# ATSAMD09D14_Breakout_rev_B.net
KiCad netlist of a schematic drawn in EAGLE
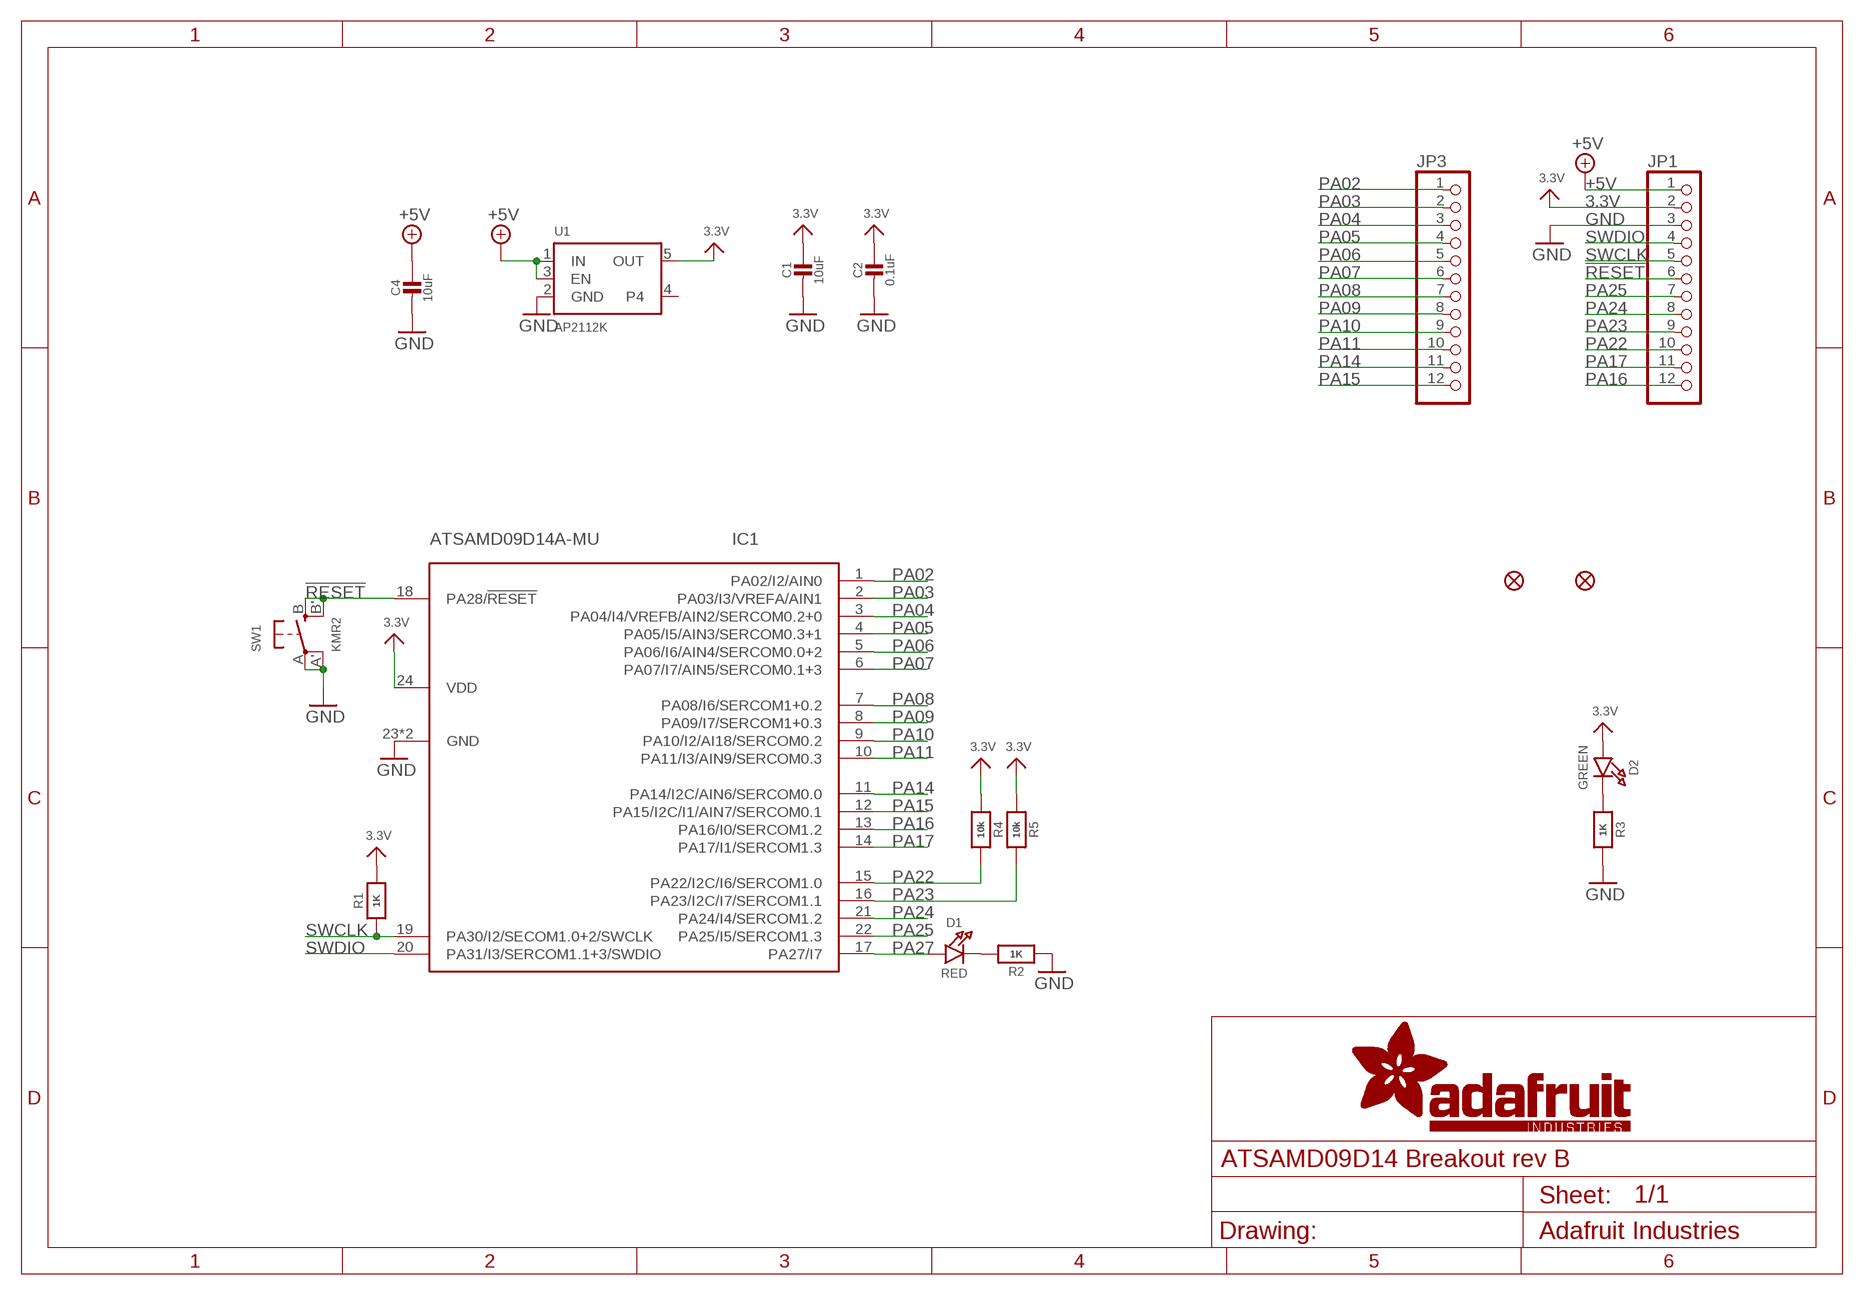
[diagram p0: schematic, sheet 1]

(export (version "E")
  (design (tool "Eeschema 10.0.6"))
  (components
    (comp (ref "C1")
      (value "10uF")
      (footprint "eagle-import:0805-NO")
      (libsource (lib "eagle-import") (part "CAP_CERAMIC0805-NOOUTLINE"))
    )
    (comp (ref "C2")
      (value "0.1uF")
      (footprint "eagle-import:0603-NO")
      (libsource (lib "eagle-import") (part "CAP_CERAMIC0603_NO"))
    )
    (comp (ref "C4")
      (value "10uF")
      (footprint "eagle-import:0805-NO")
      (libsource (lib "eagle-import") (part "CAP_CERAMIC0805-NOOUTLINE"))
    )
    (comp (ref "D1")
      (value "RED")
      (footprint "eagle-import:CHIPLED_0805_NOOUTLINE")
      (libsource (lib "eagle-import") (part "LED0805_NOOUTLINE"))
    )
    (comp (ref "D2")
      (value "GREEN")
      (footprint "eagle-import:CHIPLED_0805_NOOUTLINE")
      (libsource (lib "eagle-import") (part "LED0805_NOOUTLINE"))
    )
    (comp (ref "FID1")
      (value "FIDUCIAL\"\"")
      (footprint "eagle-import:FIDUCIAL_1MM")
      (libsource (lib "eagle-import") (part "FIDUCIAL{dblquote}{dblquote}"))
    )
    (comp (ref "FID2")
      (value "FIDUCIAL\"\"")
      (footprint "eagle-import:FIDUCIAL_1MM")
      (libsource (lib "eagle-import") (part "FIDUCIAL{dblquote}{dblquote}"))
    )
    (comp (ref "IC1")
      (value "ATSAMD09D14A-MU")
      (footprint "eagle-import:QFN24_4MM")
      (libsource (lib "eagle-import") (part "ATSAMD09D14A-MU"))
    )
    (comp (ref "JP1")
      (value "HEADER-1X1276MIL")
      (footprint "eagle-import:1X12_ROUND_76MIL")
      (libsource (lib "eagle-import") (part "HEADER-1X1276MIL"))
    )
    (comp (ref "JP3")
      (value "HEADER-1X1276MIL")
      (footprint "eagle-import:1X12_ROUND_76MIL")
      (libsource (lib "eagle-import") (part "HEADER-1X1276MIL"))
    )
    (comp (ref "R1")
      (value "1K")
      (footprint "eagle-import:0603-NO")
      (libsource (lib "eagle-import") (part "RESISTOR_0603_NOOUT"))
    )
    (comp (ref "R2")
      (value "1K")
      (footprint "eagle-import:0603-NO")
      (libsource (lib "eagle-import") (part "RESISTOR_0603_NOOUT"))
    )
    (comp (ref "R3")
      (value "1K")
      (footprint "eagle-import:0603-NO")
      (libsource (lib "eagle-import") (part "RESISTOR_0603_NOOUT"))
    )
    (comp (ref "R4")
      (value "10k")
      (footprint "eagle-import:0603-NO")
      (libsource (lib "eagle-import") (part "RESISTOR_0603_NOOUT"))
    )
    (comp (ref "R5")
      (value "10k")
      (footprint "eagle-import:0603-NO")
      (libsource (lib "eagle-import") (part "RESISTOR_0603_NOOUT"))
    )
    (comp (ref "SW1")
      (value "KMR2")
      (footprint "eagle-import:BTN_KMR2_4.6X2.8")
      (libsource (lib "eagle-import") (part "SWITCH_TACT_SMT4.6X2.8"))
    )
    (comp (ref "U1")
      (value "AP2112K")
      (footprint "eagle-import:SOT23-5")
      (libsource (lib "eagle-import") (part "VREG_SOT23-5"))
    )
  )
  (nets
    (net (code "1") (name "+5V") (class "Default")
      (node (ref "C4") (pin "1") (pinfunction "1_1") (pintype "passive"))
      (node (ref "JP1") (pin "1") (pinfunction "1_1") (pintype "passive"))
      (node (ref "U1") (pin "1") (pinfunction "IN_1") (pintype "power_in"))
      (node (ref "U1") (pin "3") (pinfunction "EN_3") (pintype "input"))
    )
    (net (code "2") (name "/PA02") (class "Default")
      (node (ref "IC1") (pin "1") (pinfunction "PA02/I2/AIN0_1") (pintype "bidirectional"))
      (node (ref "JP3") (pin "1") (pinfunction "1_1") (pintype "passive"))
    )
    (net (code "3") (name "/PA03") (class "Default")
      (node (ref "IC1") (pin "2") (pinfunction "PA03/I3/VREFA/AIN1_2") (pintype "bidirectional"))
      (node (ref "JP3") (pin "2") (pinfunction "2_2") (pintype "passive"))
    )
    (net (code "4") (name "/PA04") (class "Default")
      (node (ref "IC1") (pin "3") (pinfunction "PA04/I4/VREFB/AIN2/SERCOM0.2+0_3") (pintype "bidirectional"))
      (node (ref "JP3") (pin "3") (pinfunction "3_3") (pintype "passive"))
    )
    (net (code "5") (name "/PA05") (class "Default")
      (node (ref "IC1") (pin "4") (pinfunction "PA05/I5/AIN3/SERCOM0.3+1_4") (pintype "bidirectional"))
      (node (ref "JP3") (pin "4") (pinfunction "4_4") (pintype "passive"))
    )
    (net (code "6") (name "/PA06") (class "Default")
      (node (ref "IC1") (pin "5") (pinfunction "PA06/I6/AIN4/SERCOM0.0+2_5") (pintype "bidirectional"))
      (node (ref "JP3") (pin "5") (pinfunction "5_5") (pintype "passive"))
    )
    (net (code "7") (name "/PA07") (class "Default")
      (node (ref "IC1") (pin "6") (pinfunction "PA07/I7/AIN5/SERCOM0.1+3_6") (pintype "bidirectional"))
      (node (ref "JP3") (pin "6") (pinfunction "6_6") (pintype "passive"))
    )
    (net (code "8") (name "/PA08") (class "Default")
      (node (ref "IC1") (pin "7") (pinfunction "PA08/I6/SERCOM1+0.2_7") (pintype "bidirectional"))
      (node (ref "JP3") (pin "7") (pinfunction "7_7") (pintype "passive"))
    )
    (net (code "9") (name "/PA09") (class "Default")
      (node (ref "IC1") (pin "8") (pinfunction "PA09/I7/SERCOM1+0.3_8") (pintype "bidirectional"))
      (node (ref "JP3") (pin "8") (pinfunction "8_8") (pintype "passive"))
    )
    (net (code "10") (name "/PA10") (class "Default")
      (node (ref "IC1") (pin "9") (pinfunction "PA10/I2/AI18/SERCOM0.2_9") (pintype "bidirectional"))
      (node (ref "JP3") (pin "9") (pinfunction "9_9") (pintype "passive"))
    )
    (net (code "11") (name "/PA11") (class "Default")
      (node (ref "IC1") (pin "10") (pinfunction "PA11/I3/AIN9/SERCOM0.3_10") (pintype "bidirectional"))
      (node (ref "JP3") (pin "10") (pinfunction "10_10") (pintype "passive"))
    )
    (net (code "12") (name "/PA14") (class "Default")
      (node (ref "IC1") (pin "11") (pinfunction "PA14/I2C/AIN6/SERCOM0.0_11") (pintype "bidirectional"))
      (node (ref "JP3") (pin "11") (pinfunction "11_11") (pintype "passive"))
    )
    (net (code "13") (name "/PA15") (class "Default")
      (node (ref "IC1") (pin "12") (pinfunction "PA15/I2C/I1/AIN7/SERCOM0.1_12") (pintype "bidirectional"))
      (node (ref "JP3") (pin "12") (pinfunction "12_12") (pintype "passive"))
    )
    (net (code "14") (name "/PA16") (class "Default")
      (node (ref "IC1") (pin "13") (pinfunction "PA16/I0/SERCOM1.2_13") (pintype "bidirectional"))
      (node (ref "JP1") (pin "12") (pinfunction "12_12") (pintype "passive"))
    )
    (net (code "15") (name "/PA17") (class "Default")
      (node (ref "IC1") (pin "14") (pinfunction "PA17/I1/SERCOM1.3_14") (pintype "bidirectional"))
      (node (ref "JP1") (pin "11") (pinfunction "11_11") (pintype "passive"))
    )
    (net (code "16") (name "/PA22") (class "Default")
      (node (ref "IC1") (pin "15") (pinfunction "PA22/I2C/I6/SERCOM1.0_15") (pintype "bidirectional"))
      (node (ref "JP1") (pin "10") (pinfunction "10_10") (pintype "passive"))
      (node (ref "R4") (pin "2") (pinfunction "2_2") (pintype "passive"))
    )
    (net (code "17") (name "/PA23") (class "Default")
      (node (ref "IC1") (pin "16") (pinfunction "PA23/I2C/I7/SERCOM1.1_16") (pintype "bidirectional"))
      (node (ref "JP1") (pin "9") (pinfunction "9_9") (pintype "passive"))
      (node (ref "R5") (pin "2") (pinfunction "2_2") (pintype "passive"))
    )
    (net (code "18") (name "/PA24") (class "Default")
      (node (ref "IC1") (pin "21") (pinfunction "PA24/I4/SERCOM1.2_21") (pintype "bidirectional"))
      (node (ref "JP1") (pin "8") (pinfunction "8_8") (pintype "passive"))
    )
    (net (code "19") (name "/PA25") (class "Default")
      (node (ref "IC1") (pin "22") (pinfunction "PA25/I5/SERCOM1.3_22") (pintype "bidirectional"))
      (node (ref "JP1") (pin "7") (pinfunction "7_7") (pintype "passive"))
    )
    (net (code "20") (name "/PA27") (class "Default")
      (node (ref "D1") (pin "A") (pinfunction "A_A") (pintype "passive"))
      (node (ref "IC1") (pin "17") (pinfunction "PA27/I7_17") (pintype "bidirectional"))
    )
    (net (code "21") (name "/SWCLK") (class "Default")
      (node (ref "IC1") (pin "19") (pinfunction "PA30/I2/SECOM1.0+2/SWCLK_19") (pintype "bidirectional"))
      (node (ref "JP1") (pin "5") (pinfunction "5_5") (pintype "passive"))
      (node (ref "R1") (pin "1") (pinfunction "1_1") (pintype "passive"))
    )
    (net (code "22") (name "/SWDIO") (class "Default")
      (node (ref "IC1") (pin "20") (pinfunction "PA31/I3/SERCOM1.1+3/SWDIO_20") (pintype "bidirectional"))
      (node (ref "JP1") (pin "4") (pinfunction "4_4") (pintype "passive"))
    )
    (net (code "23") (name "/~{RESET}") (class "Default")
      (node (ref "IC1") (pin "18") (pinfunction "PA28/~{RESET}_18") (pintype "bidirectional"))
      (node (ref "JP1") (pin "6") (pinfunction "6_6") (pintype "passive"))
      (node (ref "SW1") (pin "B") (pinfunction "S_B") (pintype "passive"))
      (node (ref "SW1") (pin "B'") (pinfunction "S1_B'") (pintype "passive"))
    )
    (net (code "24") (name "3.3V") (class "Default")
      (node (ref "C1") (pin "1") (pinfunction "1_1") (pintype "passive"))
      (node (ref "C2") (pin "1") (pinfunction "1_1") (pintype "passive"))
      (node (ref "D2") (pin "A") (pinfunction "A_A") (pintype "passive"))
      (node (ref "IC1") (pin "24") (pinfunction "VDD_24") (pintype "power_in"))
      (node (ref "JP1") (pin "2") (pinfunction "2_2") (pintype "passive"))
      (node (ref "R1") (pin "2") (pinfunction "2_2") (pintype "passive"))
      (node (ref "R4") (pin "1") (pinfunction "1_1") (pintype "passive"))
      (node (ref "R5") (pin "1") (pinfunction "1_1") (pintype "passive"))
      (node (ref "U1") (pin "5") (pinfunction "OUT_5") (pintype "power_in"))
    )
    (net (code "25") (name "GND") (class "Default")
      (node (ref "C1") (pin "2") (pinfunction "2_2") (pintype "passive"))
      (node (ref "C2") (pin "2") (pinfunction "2_2") (pintype "passive"))
      (node (ref "C4") (pin "2") (pinfunction "2_2") (pintype "passive"))
      (node (ref "IC1") (pin "23") (pinfunction "GND_23") (pintype "power_in"))
      (node (ref "IC1") (pin "THERM") (pinfunction "GND_THERM") (pintype "power_in"))
      (node (ref "JP1") (pin "3") (pinfunction "3_3") (pintype "passive"))
      (node (ref "R2") (pin "1") (pinfunction "1_1") (pintype "passive"))
      (node (ref "R3") (pin "2") (pinfunction "2_2") (pintype "passive"))
      (node (ref "SW1") (pin "A") (pinfunction "P_A") (pintype "passive"))
      (node (ref "SW1") (pin "A'") (pinfunction "P1_A'") (pintype "passive"))
      (node (ref "U1") (pin "2") (pinfunction "GND_2") (pintype "power_in"))
    )
    (net (code "26") (name "Net-(D1-PadC)") (class "Default")
      (node (ref "D1") (pin "C") (pinfunction "C_C") (pintype "passive"))
      (node (ref "R2") (pin "2") (pinfunction "2_2") (pintype "passive"))
    )
    (net (code "27") (name "Net-(D2-PadC)") (class "Default")
      (node (ref "D2") (pin "C") (pinfunction "C_C") (pintype "passive"))
      (node (ref "R3") (pin "1") (pinfunction "1_1") (pintype "passive"))
    )
    (net (code "28") (name "unconnected-(U1-P4-Pad4)") (class "Default")
      (node (ref "U1") (pin "4") (pinfunction "P4_4") (pintype "bidirectional"))
    )
  )
)
